# Amp.net
KiCad netlist of a schematic drawn in Altium Designer
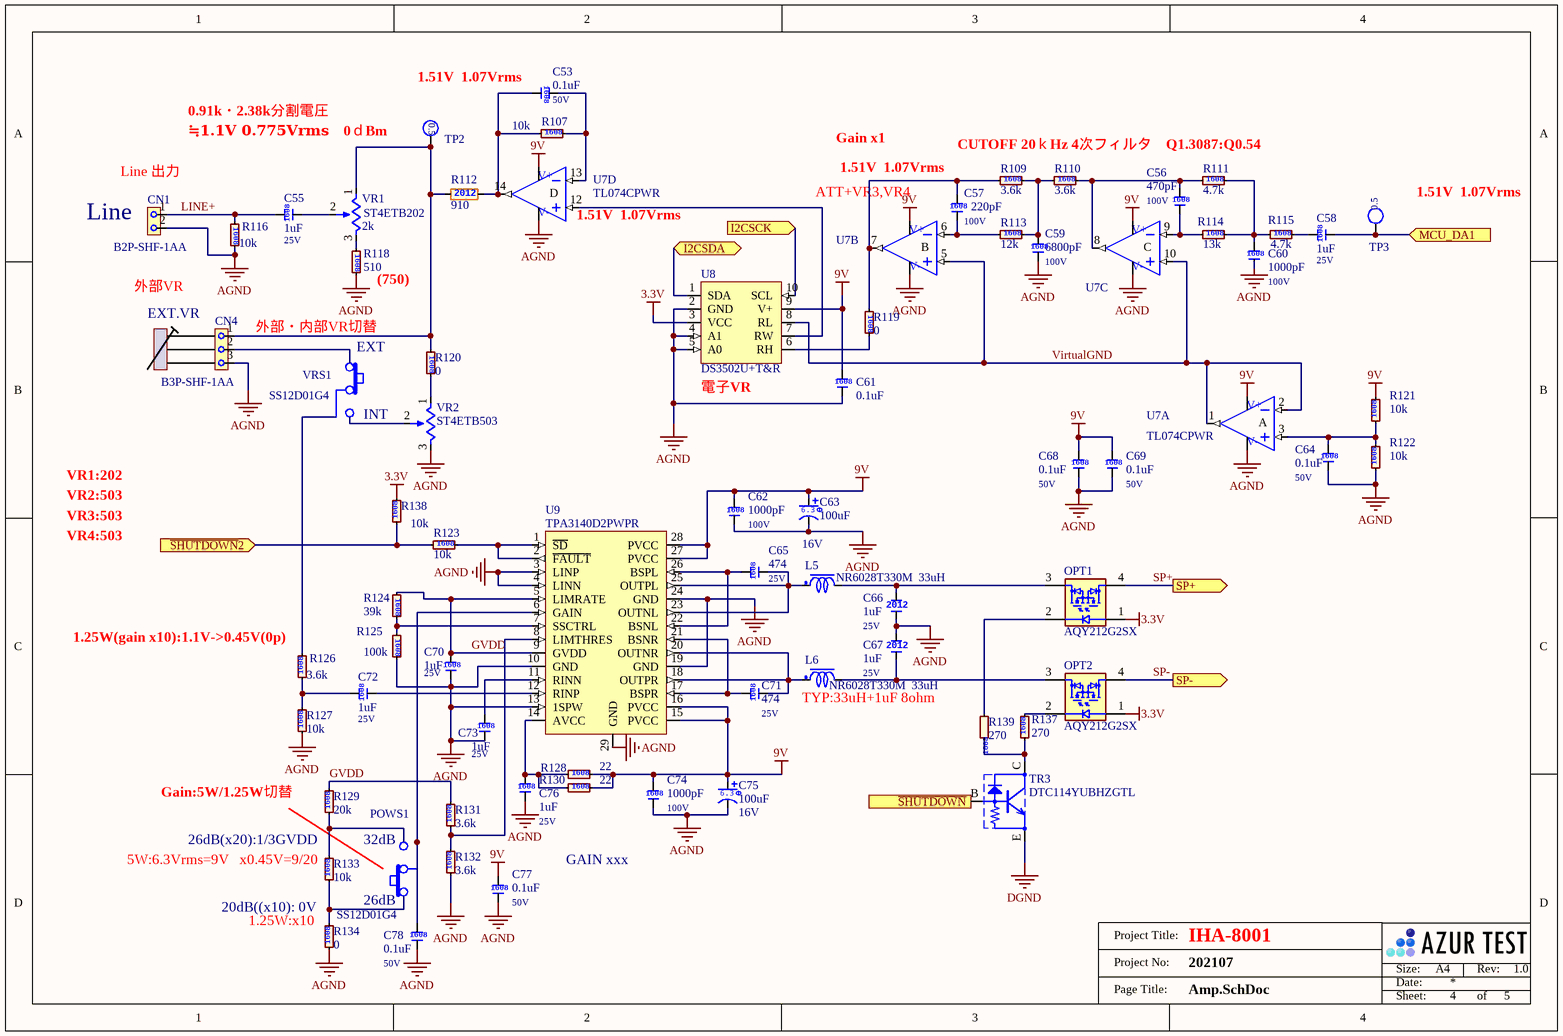
[diagram p0: Amp.SchDoc]

(export (version "E")
  (design (tool "Eeschema 10.0.6"))
  (components
    (comp (ref "C53")
      (value "CGA3E2X7R1H104K080AA")
      (footprint "C1608")
      (description "セラコン1608サイズ")
      (fields (field (name "TAG") "0.1uF") (field (name "VOLTAGE") "50V"))
      (libsource (lib "Audio Prj") (part "C1608"))
    )
    (comp (ref "C55")
      (value "TMK107BJ105MA-T")
      (footprint "C1608")
      (description "セラコン1608サイズ")
      (fields (field (name "TAG") "1uF") (field (name "VOLTAGE") "25V"))
      (libsource (lib "Audio Prj") (part "C1608"))
    )
    (comp (ref "C56")
      (value "GCM1885C2A471JA16D")
      (footprint "C1608")
      (description "セラコン1608サイズ")
      (fields (field (name "TAG") "470pF") (field (name "VOLTAGE") "100V"))
      (libsource (lib "Audio Prj") (part "C1608"))
    )
    (comp (ref "C57")
      (value "GCM1885C2A221JA16D")
      (footprint "C1608")
      (description "セラコン1608サイズ")
      (fields (field (name "TAG") "220pF") (field (name "VOLTAGE") "100V"))
      (libsource (lib "Audio Prj") (part "C1608"))
    )
    (comp (ref "C58")
      (value "TMK107BJ105MA-T")
      (footprint "C1608")
      (description "セラコン1608サイズ")
      (fields (field (name "TAG") "1uF") (field (name "VOLTAGE") "25V"))
      (libsource (lib "Audio Prj") (part "C1608"))
    )
    (comp (ref "C59")
      (value "GCM1885C2A682JA16D")
      (footprint "C1608")
      (description "セラコン1608サイズ")
      (fields (field (name "TAG") "6800pF") (field (name "VOLTAGE") "100V"))
      (libsource (lib "Audio Prj") (part "C1608"))
    )
    (comp (ref "C60")
      (value "GCM1885C2A102JA16D")
      (footprint "C1608")
      (description "セラコン1608サイズ")
      (fields (field (name "TAG") "1000pF") (field (name "VOLTAGE") "100V"))
      (libsource (lib "Audio Prj") (part "C1608"))
    )
    (comp (ref "C61")
      (value "CGA3E2X7R1H104K080AA")
      (footprint "C1608")
      (description "セラコン1608サイズ")
      (fields (field (name "TAG") "0.1uF") (field (name "VOLTAGE") "50V"))
      (libsource (lib "Audio Prj") (part "C1608"))
    )
    (comp (ref "C62")
      (value "GCM1885C2A102JA16D")
      (footprint "C1608")
      (description "セラコン1608サイズ")
      (fields (field (name "TAG") "1000pF") (field (name "VOLTAGE") "100V"))
      (libsource (lib "Audio Prj") (part "C1608"))
    )
    (comp (ref "C63")
      (value "UCQ1C101MCL1GS")
      (footprint "6.6mmX6.6mm")
      (description "6.3φ 電解コンデンサ")
      (fields (field (name "TAG") "100uF") (field (name "VOLTAGE") "16V"))
      (libsource (lib "Audio Prj") (part "6.6 X 6.6"))
    )
    (comp (ref "C64")
      (value "CGA3E2X7R1H104K080AA")
      (footprint "C1608")
      (description "セラコン1608サイズ")
      (fields (field (name "TAG") "0.1uF") (field (name "VOLTAGE") "50V"))
      (libsource (lib "Audio Prj") (part "C1608"))
    )
    (comp (ref "C65")
      (value "UMK107B7474KA-TR")
      (footprint "C1608")
      (description "セラコン1608サイズ")
      (fields (field (name "TAG") "474") (field (name "VOLTAGE") "25V"))
      (libsource (lib "Audio Prj") (part "C1608"))
    )
    (comp (ref "C66")
      (value "TMK212BJ105KG-T")
      (footprint "C2012")
      (description "セラコン2012サイズ")
      (fields (field (name "TAG") "1uF") (field (name "VOLTAGE") "25V"))
      (libsource (lib "Audio") (part "C2012"))
    )
    (comp (ref "C67")
      (value "TMK212BJ105KG-T")
      (footprint "C2012")
      (description "セラコン2012サイズ")
      (fields (field (name "TAG") "1uF") (field (name "VOLTAGE") "25V"))
      (libsource (lib "Audio") (part "C2012"))
    )
    (comp (ref "C68")
      (value "CGA3E2X7R1H104K080AA")
      (footprint "C1608")
      (description "セラコン1608サイズ")
      (fields (field (name "TAG") "0.1uF") (field (name "VOLTAGE") "50V"))
      (libsource (lib "Audio Prj") (part "C1608"))
    )
    (comp (ref "C69")
      (value "CGA3E2X7R1H104K080AA")
      (footprint "C1608")
      (description "セラコン1608サイズ")
      (fields (field (name "TAG") "0.1uF") (field (name "VOLTAGE") "50V"))
      (libsource (lib "Audio Prj") (part "C1608"))
    )
    (comp (ref "C70")
      (value "TMK107BJ105MA-T")
      (footprint "C1608")
      (description "セラコン1608サイズ")
      (fields (field (name "TAG") "1uF") (field (name "VOLTAGE") "25V"))
      (libsource (lib "Audio Prj") (part "C1608"))
    )
    (comp (ref "C71")
      (value "UMK107B7474KA-TR")
      (footprint "C1608")
      (description "セラコン1608サイズ")
      (fields (field (name "TAG") "474") (field (name "VOLTAGE") "25V"))
      (libsource (lib "Audio Prj") (part "C1608"))
    )
    (comp (ref "C72")
      (value "TMK107BJ105MA-T")
      (footprint "C1608")
      (description "セラコン1608サイズ")
      (fields (field (name "TAG") "1uF") (field (name "VOLTAGE") "25V"))
      (libsource (lib "Audio Prj") (part "C1608"))
    )
    (comp (ref "C73")
      (value "TMK107BJ105MA-T")
      (footprint "C1608")
      (description "セラコン1608サイズ")
      (fields (field (name "TAG") "1uF") (field (name "VOLTAGE") "25V"))
      (libsource (lib "Audio Prj") (part "C1608"))
    )
    (comp (ref "C74")
      (value "GCM1885C2A102JA16D")
      (footprint "C1608")
      (description "セラコン1608サイズ")
      (fields (field (name "TAG") "1000pF") (field (name "VOLTAGE") "100V"))
      (libsource (lib "Audio Prj") (part "C1608"))
    )
    (comp (ref "C75")
      (value "UCQ1C101MCL1GS")
      (footprint "6.6mmX6.6mm")
      (description "6.3φ 電解コンデンサ")
      (fields (field (name "TAG") "100uF") (field (name "VOLTAGE") "16V"))
      (libsource (lib "Audio Prj") (part "6.6 X 6.6"))
    )
    (comp (ref "C76")
      (value "TMK107BJ105MA-T")
      (footprint "C1608")
      (description "セラコン1608サイズ")
      (fields (field (name "TAG") "1uF") (field (name "VOLTAGE") "25V"))
      (libsource (lib "Audio Prj") (part "C1608"))
    )
    (comp (ref "C77")
      (value "CGA3E2X7R1H104K080AA")
      (footprint "C1608")
      (description "セラコン1608サイズ")
      (fields (field (name "TAG") "0.1uF") (field (name "VOLTAGE") "50V"))
      (libsource (lib "Audio Prj") (part "C1608"))
    )
    (comp (ref "C78")
      (value "CGA3E2X7R1H104K080AA")
      (footprint "C1608")
      (description "セラコン1608サイズ")
      (fields (field (name "TAG") "0.1uF") (field (name "VOLTAGE") "50V"))
      (libsource (lib "Audio Prj") (part "C1608"))
    )
    (comp (ref "CN1")
      (value "B2P-SHF-1AA")
      (footprint "B2P-SHF-1AA")
      (description "雄,ストレート,1列2ピン")
      (libsource (lib "Audio Prj") (part "B2P-SHF-1AA"))
    )
    (comp (ref "CN4")
      (value "B3P-SHF-1AA")
      (footprint "B3P-SHF-1AA")
      (description "雄,ストレート,1列3ピン")
      (libsource (lib "Audio Prj") (part "B3P-SHF-1AA"))
    )
    (comp (ref "L5")
      (value "NR6028T330M  33uH")
      (footprint "NR6028T")
      (description "Shielded Inductor")
      (libsource (lib "Audio Prj") (part "DR125"))
    )
    (comp (ref "L6")
      (value "NR6028T330M  33uH")
      (footprint "NR6028T")
      (description "Shielded Inductor")
      (libsource (lib "Audio Prj") (part "DR125"))
    )
    (comp (ref "OPT1")
      (value "AQY212G2SX")
      (footprint "SOP4-2.54")
      (description "60V 550mA フォトモス")
      (libsource (lib "Audio Prj") (part "AQY225R2S"))
    )
    (comp (ref "OPT2")
      (value "AQY212G2SX")
      (footprint "SOP4-2.54")
      (description "60V 550mA フォトモス")
      (libsource (lib "Audio Prj") (part "AQY225R2S"))
    )
    (comp (ref "POWS1")
      (value "SS12D01G4")
      (footprint "SS12D01G4")
      (description "SPDTスライドスイッチ")
      (libsource (lib "Audio Prj") (part "SS12D01G4"))
    )
    (comp (ref "R107")
      (value "ERJ-PA3F1002V")
      (footprint "R1608")
      (description "厚膜チップ抵抗1608サイズ")
      (fields (field (name "TAG") "10k"))
      (libsource (lib "") (part "TF1608_2"))
    )
    (comp (ref "R109")
      (value "ERJ-PA3F3601V")
      (footprint "R1608")
      (description "厚膜チップ抵抗1608サイズ")
      (fields (field (name "TAG") "3.6k"))
      (libsource (lib "") (part "TF1608_2"))
    )
    (comp (ref "R110")
      (value "ERJ-PA3F3601V")
      (footprint "R1608")
      (description "厚膜チップ抵抗1608サイズ")
      (fields (field (name "TAG") "3.6k"))
      (libsource (lib "") (part "TF1608_2"))
    )
    (comp (ref "R111")
      (value "ERJ-PA3F4701V")
      (footprint "R1608")
      (description "厚膜チップ抵抗1608サイズ")
      (fields (field (name "TAG") "4.7k"))
      (libsource (lib "") (part "TF1608_2"))
    )
    (comp (ref "R112")
      (value "RK73B2ATTD911J")
      (footprint "R2012")
      (description "薄膜チップ抵抗2012サイズ")
      (fields (field (name "TAG") "910"))
      (libsource (lib "Audio Prj") (part "MF2012"))
    )
    (comp (ref "R113")
      (value "ERJ-PA3F1201V")
      (footprint "R1608")
      (description "厚膜チップ抵抗1608サイズ")
      (fields (field (name "TAG") "12k"))
      (libsource (lib "") (part "TF1608_2"))
    )
    (comp (ref "R114")
      (value "ERJ-PA3F1302V")
      (footprint "R1608")
      (description "厚膜チップ抵抗1608サイズ")
      (fields (field (name "TAG") "13k"))
      (libsource (lib "") (part "TF1608_2"))
    )
    (comp (ref "R115")
      (value "ERJ-PA3F4701V")
      (footprint "R1608")
      (description "厚膜チップ抵抗1608サイズ")
      (fields (field (name "TAG") "4.7k"))
      (libsource (lib "") (part "TF1608_2"))
    )
    (comp (ref "R116")
      (value "ERJ-PA3F1002V")
      (footprint "R1608")
      (description "厚膜チップ抵抗1608サイズ")
      (fields (field (name "TAG") "10k"))
      (libsource (lib "") (part "TF1608_1"))
    )
    (comp (ref "R118")
      (value "ERJ-PA3F5100V")
      (footprint "R1608")
      (description "厚膜チップ抵抗1608サイズ")
      (fields (field (name "TAG") "510"))
      (libsource (lib "") (part "TF1608_1"))
    )
    (comp (ref "R119")
      (value "RK73Z1JTTD")
      (footprint "R1608")
      (description "厚膜チップ抵抗1608サイズ")
      (fields (field (name "TAG") "0"))
      (libsource (lib "") (part "TF1608_1"))
    )
    (comp (ref "R120")
      (value "RK73Z1JTTD")
      (footprint "R1608")
      (description "厚膜チップ抵抗1608サイズ")
      (fields (field (name "TAG") "0"))
      (libsource (lib "") (part "TF1608_1"))
    )
    (comp (ref "R121")
      (value "ERJ-PA3F1002V")
      (footprint "R1608")
      (description "厚膜チップ抵抗1608サイズ")
      (fields (field (name "TAG") "10k"))
      (libsource (lib "Audio Prj") (part "TF1608"))
    )
    (comp (ref "R122")
      (value "ERJ-PA3F1002V")
      (footprint "R1608")
      (description "厚膜チップ抵抗1608サイズ")
      (fields (field (name "TAG") "10k"))
      (libsource (lib "Audio Prj") (part "TF1608"))
    )
    (comp (ref "R123")
      (value "ERJ-PA3F1002V")
      (footprint "R1608")
      (description "厚膜チップ抵抗1608サイズ")
      (fields (field (name "TAG") "10k"))
      (libsource (lib "") (part "TF1608_2"))
    )
    (comp (ref "R124")
      (value "ERJ-PA3F3902V")
      (footprint "R1608")
      (description "厚膜チップ抵抗1608サイズ")
      (fields (field (name "TAG") "39k"))
      (libsource (lib "") (part "TF1608_1"))
    )
    (comp (ref "R125")
      (value "ERJ-PA3F1003V")
      (footprint "R1608")
      (description "厚膜チップ抵抗1608サイズ")
      (fields (field (name "TAG") "100k"))
      (libsource (lib "") (part "TF1608_1"))
    )
    (comp (ref "R126")
      (value "ERJ-PA3F3601V")
      (footprint "R1608")
      (description "厚膜チップ抵抗1608サイズ")
      (fields (field (name "TAG") "3.6k"))
      (libsource (lib "Audio Prj") (part "TF1608"))
    )
    (comp (ref "R127")
      (value "ERJ-PA3F1002V")
      (footprint "R1608")
      (description "厚膜チップ抵抗1608サイズ")
      (fields (field (name "TAG") "10k"))
      (libsource (lib "Audio Prj") (part "TF1608"))
    )
    (comp (ref "R128")
      (value "ERJ-PA3F22R0V")
      (footprint "R1608")
      (description "厚膜チップ抵抗1608サイズ")
      (fields (field (name "TAG") "22"))
      (libsource (lib "") (part "TF1608_2"))
    )
    (comp (ref "R129")
      (value "ERJ-PA3F2002V")
      (footprint "R1608")
      (description "厚膜チップ抵抗1608サイズ")
      (fields (field (name "TAG") "20k"))
      (libsource (lib "Audio Prj") (part "TF1608"))
    )
    (comp (ref "R130")
      (value "ERJ-PA3F22R0V")
      (footprint "R1608")
      (description "厚膜チップ抵抗1608サイズ")
      (fields (field (name "TAG") "22"))
      (libsource (lib "") (part "TF1608_2"))
    )
    (comp (ref "R131")
      (value "ERJ-PA3F3601V")
      (footprint "R1608")
      (description "厚膜チップ抵抗1608サイズ")
      (fields (field (name "TAG") "3.6k"))
      (libsource (lib "Audio Prj") (part "TF1608"))
    )
    (comp (ref "R132")
      (value "ERJ-PA3F3601V")
      (footprint "R1608")
      (description "厚膜チップ抵抗1608サイズ")
      (fields (field (name "TAG") "3.6k"))
      (libsource (lib "Audio Prj") (part "TF1608"))
    )
    (comp (ref "R133")
      (value "ERJ-PA3F1002V")
      (footprint "R1608")
      (description "厚膜チップ抵抗1608サイズ")
      (fields (field (name "TAG") "10k"))
      (libsource (lib "Audio Prj") (part "TF1608"))
    )
    (comp (ref "R134")
      (value "RK73Z1JTTD")
      (footprint "R1608")
      (description "厚膜チップ抵抗1608サイズ")
      (fields (field (name "TAG") "0"))
      (libsource (lib "Audio Prj") (part "TF1608"))
    )
    (comp (ref "R137")
      (value "RR0816P-271-D")
      (footprint "R1608")
      (description "厚膜チップ抵抗1608サイズ")
      (fields (field (name "TAG") "270"))
      (libsource (lib "Audio Prj") (part "TF1608"))
    )
    (comp (ref "R138")
      (value "ERJ-PA3F1002V")
      (footprint "R1608")
      (description "厚膜チップ抵抗1608サイズ")
      (fields (field (name "TAG") "10k"))
      (libsource (lib "Audio Prj") (part "TF1608"))
    )
    (comp (ref "R139")
      (value "RR0816P-271-D")
      (footprint "R1608")
      (description "厚膜チップ抵抗1608サイズ")
      (fields (field (name "TAG") "270"))
      (libsource (lib "") (part "TF1608_2"))
    )
    (comp (ref "TP2")
      (value "TP0.5mm")
      (footprint "TP0.5mm")
      (description "Test-Point 0.5mm")
      (libsource (lib "Audio Prj") (part "TP0.5mm"))
    )
    (comp (ref "TP3")
      (value "TP0.5mm")
      (footprint "TP0.5mm")
      (description "Test-Point 0.5mm")
      (libsource (lib "Audio Prj") (part "TP0.5mm"))
    )
    (comp (ref "TR3")
      (value "DTC114YUBHZGTL")
      (footprint "SOT-323F")
      (description "NPN  TR 0.1A SC85 2x2.1 SOC323")
      (libsource (lib "Audio Prj") (part "DTC114YUBHZGTL"))
    )
    (comp (ref "U7")
      (value "TL074CPWR")
      (footprint "TSSOP14")
      (description "IC OPAMP JFET 4 CIRCUIT 14TSSOP")
      (libsource (lib "Audio Prj") (part "TL084CPT"))
    )
    (comp (ref "U8")
      (value "DS3502U+T&R")
      (footprint "MSOP10")
      (description "IC DGTL POT 10KOHM 128TAP 10UMAX")
      (libsource (lib "Audio Prj") (part "DS3502U+T&R"))
    )
    (comp (ref "U9")
      (value "TPA3140D2PWPR")
      (footprint "TSSOP28")
      (description "IC AMP CLASS D STER 10W 28HTSSOP")
      (libsource (lib "Audio Prj") (part "TPA3140D2PWPR"))
    )
    (comp (ref "VR1")
      (value "ST4ETB202")
      (footprint "ST4ETB202")
      (description "CERMET TRIMMER  Top adjustmet")
      (fields (field (name "TAG") "2k"))
      (libsource (lib "Audio Prj") (part "ST-32EA**"))
    )
    (comp (ref "VR2")
      (value "ST4ETB503")
      (footprint "ST4ETB202")
      (description "CERMET TRIMMER  Top adjustmet")
      (libsource (lib "Audio Prj") (part "ST-32EA**"))
    )
    (comp (ref "VRS1")
      (value "SS12D01G4")
      (footprint "SS12D01G4")
      (description "SPDTスライドスイッチ")
      (libsource (lib "Audio Prj") (part "SS12D01G4"))
    )
  )
  (nets
    (net (code "1") (name "/GVDD") (class "Default")
      (node (ref "C70") (pin "2") (pinfunction "2_2") (pintype "passive"))
      (node (ref "R124") (pin "1") (pinfunction "1_1") (pintype "passive"))
      (node (ref "R129") (pin "2") (pinfunction "2_2") (pintype "passive"))
      (node (ref "R131") (pin "2") (pinfunction "2_2") (pintype "passive"))
      (node (ref "U9") (pin "5") (pinfunction "LIMRATE_5") (pintype "input"))
      (node (ref "U9") (pin "9") (pinfunction "GVDD_9") (pintype "power_in"))
    )
    (net (code "2") (name "/I2CSCK") (class "Default")
      (node (ref "U8") (pin "10") (pinfunction "SCL_10") (pintype "input"))
    )
    (net (code "3") (name "/I2CSDA") (class "Default")
      (node (ref "U8") (pin "1") (pinfunction "SDA_1") (pintype "bidirectional"))
    )
    (net (code "4") (name "/LINE+") (class "Default")
      (node (ref "C55") (pin "2") (pinfunction "2_2") (pintype "passive"))
      (node (ref "CN1") (pin "1") (pinfunction "1_1") (pintype "passive"))
      (node (ref "R116") (pin "1") (pinfunction "1_1") (pintype "passive"))
    )
    (net (code "5") (name "/MCU_DA1") (class "Default")
      (node (ref "C58") (pin "1") (pinfunction "1_1") (pintype "passive"))
      (node (ref "TP3") (pin "1") (pinfunction "1_1") (pintype "passive"))
    )
    (net (code "6") (name "/SP+") (class "Default")
      (node (ref "OPT1") (pin "4") (pinfunction "4_4") (pintype "passive"))
    )
    (net (code "7") (name "/SP-") (class "Default")
      (node (ref "OPT2") (pin "4") (pinfunction "4_4") (pintype "passive"))
    )
    (net (code "8") (name "/VirtualGND") (class "Default")
      (node (ref "U7") (pin "1") (pinfunction "OUT_1") (pintype "output"))
      (node (ref "U7") (pin "10") (pinfunction "IN+_10") (pintype "input"))
      (node (ref "U7") (pin "2") (pinfunction "IN-_2") (pintype "input"))
      (node (ref "U7") (pin "5") (pinfunction "IN+_5") (pintype "input"))
      (node (ref "U8") (pin "8") (pinfunction "RL_8") (pintype "passive"))
    )
    (net (code "9") (name "/~{SHUTDOWN}") (class "Default")
      (node (ref "TR3") (pin "B") (pinfunction "IN_B") (pintype "passive"))
    )
    (net (code "10") (name "/~{SHUTDOWN}2") (class "Default")
      (node (ref "R123") (pin "1") (pinfunction "1_1") (pintype "passive"))
      (node (ref "R138") (pin "1") (pinfunction "1_1") (pintype "passive"))
    )
    (net (code "11") (name "3.3V") (class "Default")
      (node (ref "OPT1") (pin "1") (pinfunction "1_1") (pintype "passive"))
      (node (ref "OPT2") (pin "1") (pinfunction "1_1") (pintype "passive"))
      (node (ref "R138") (pin "2") (pinfunction "2_2") (pintype "passive"))
      (node (ref "U8") (pin "3") (pinfunction "VCC_3") (pintype "power_in"))
    )
    (net (code "12") (name "9V") (class "Default")
      (node (ref "C61") (pin "2") (pinfunction "2_2") (pintype "passive"))
      (node (ref "C62") (pin "2") (pinfunction "2_2") (pintype "passive"))
      (node (ref "C63") (pin "+") (pinfunction "1_+") (pintype "passive"))
      (node (ref "C68") (pin "2") (pinfunction "2_2") (pintype "passive"))
      (node (ref "C69") (pin "2") (pinfunction "2_2") (pintype "passive"))
      (node (ref "C74") (pin "2") (pinfunction "2_2") (pintype "passive"))
      (node (ref "C75") (pin "+") (pinfunction "1_+") (pintype "passive"))
      (node (ref "C77") (pin "2") (pinfunction "2_2") (pintype "passive"))
      (node (ref "R121") (pin "2") (pinfunction "2_2") (pintype "passive"))
      (node (ref "R128") (pin "2") (pinfunction "2_2") (pintype "passive"))
      (node (ref "R130") (pin "2") (pinfunction "2_2") (pintype "passive"))
      (node (ref "U7") (pin "4") (pinfunction "V+_4") (pintype "power_in"))
      (node (ref "U8") (pin "9") (pinfunction "V+_9") (pintype "power_in"))
      (node (ref "U9") (pin "15") (pinfunction "PVCC_15") (pintype "power_in"))
      (node (ref "U9") (pin "16") (pinfunction "PVCC_16") (pintype "power_in"))
      (node (ref "U9") (pin "27") (pinfunction "PVCC_27") (pintype "power_in"))
      (node (ref "U9") (pin "28") (pinfunction "PVCC_28") (pintype "power_in"))
    )
    (net (code "13") (name "AGND") (class "Default")
      (node (ref "C59") (pin "1") (pinfunction "1_1") (pintype "passive"))
      (node (ref "C60") (pin "1") (pinfunction "1_1") (pintype "passive"))
      (node (ref "C61") (pin "1") (pinfunction "1_1") (pintype "passive"))
      (node (ref "C62") (pin "1") (pinfunction "1_1") (pintype "passive"))
      (node (ref "C63") (pin "-") (pinfunction "2_-") (pintype "passive"))
      (node (ref "C64") (pin "1") (pinfunction "1_1") (pintype "passive"))
      (node (ref "C66") (pin "1") (pinfunction "1_1") (pintype "passive"))
      (node (ref "C67") (pin "2") (pinfunction "2_2") (pintype "passive"))
      (node (ref "C68") (pin "1") (pinfunction "1_1") (pintype "passive"))
      (node (ref "C69") (pin "1") (pinfunction "1_1") (pintype "passive"))
      (node (ref "C70") (pin "1") (pinfunction "1_1") (pintype "passive"))
      (node (ref "C73") (pin "1") (pinfunction "1_1") (pintype "passive"))
      (node (ref "C74") (pin "1") (pinfunction "1_1") (pintype "passive"))
      (node (ref "C75") (pin "-") (pinfunction "2_-") (pintype "passive"))
      (node (ref "C76") (pin "1") (pinfunction "1_1") (pintype "passive"))
      (node (ref "C77") (pin "1") (pinfunction "1_1") (pintype "passive"))
      (node (ref "C78") (pin "1") (pinfunction "1_1") (pintype "passive"))
      (node (ref "CN1") (pin "2") (pinfunction "2_2") (pintype "passive"))
      (node (ref "CN4") (pin "3") (pinfunction "3_3") (pintype "passive"))
      (node (ref "R116") (pin "2") (pinfunction "2_2") (pintype "passive"))
      (node (ref "R118") (pin "2") (pinfunction "2_2") (pintype "passive"))
      (node (ref "R122") (pin "1") (pinfunction "1_1") (pintype "passive"))
      (node (ref "R125") (pin "2") (pinfunction "2_2") (pintype "passive"))
      (node (ref "R127") (pin "1") (pinfunction "1_1") (pintype "passive"))
      (node (ref "R132") (pin "1") (pinfunction "1_1") (pintype "passive"))
      (node (ref "R134") (pin "1") (pinfunction "1_1") (pintype "passive"))
      (node (ref "U7") (pin "11") (pinfunction "V-_11") (pintype "power_in"))
      (node (ref "U8") (pin "2") (pinfunction "GND_2") (pintype "power_in"))
      (node (ref "U8") (pin "4") (pinfunction "A1_4") (pintype "input"))
      (node (ref "U8") (pin "5") (pinfunction "A0_5") (pintype "input"))
      (node (ref "U9") (pin "10") (pinfunction "GND_10") (pintype "power_in"))
      (node (ref "U9") (pin "13") (pinfunction "1SPW_13") (pintype "input"))
      (node (ref "U9") (pin "19") (pinfunction "GND_19") (pintype "power_in"))
      (node (ref "U9") (pin "24") (pinfunction "GND_24") (pintype "power_in"))
      (node (ref "U9") (pin "29") (pinfunction "GND_29") (pintype "power_in"))
      (node (ref "U9") (pin "3") (pinfunction "LINP_3") (pintype "input"))
      (node (ref "U9") (pin "4") (pinfunction "LINN_4") (pintype "input"))
      (node (ref "VR2") (pin "3") (pinfunction "3_3") (pintype "passive"))
    )
    (net (code "14") (name "DGND") (class "Default")
      (node (ref "TR3") (pin "E") (pinfunction "E_E") (pintype "passive"))
    )
    (net (code "15") (name "Net-(C55-Pad1)") (class "Default")
      (node (ref "C55") (pin "1") (pinfunction "1_1") (pintype "passive"))
      (node (ref "VR1") (pin "2") (pinfunction "2_2") (pintype "passive"))
    )
    (net (code "16") (name "Net-(C58-Pad2)") (class "Default")
      (node (ref "C58") (pin "2") (pinfunction "2_2") (pintype "passive"))
      (node (ref "R115") (pin "2") (pinfunction "2_2") (pintype "passive"))
    )
    (net (code "17") (name "Net-(C59-Pad2)") (class "Default")
      (node (ref "C59") (pin "2") (pinfunction "2_2") (pintype "passive"))
      (node (ref "R109") (pin "2") (pinfunction "2_2") (pintype "passive"))
      (node (ref "R110") (pin "1") (pinfunction "1_1") (pintype "passive"))
      (node (ref "R113") (pin "2") (pinfunction "2_2") (pintype "passive"))
    )
    (net (code "18") (name "Net-(C60-Pad2)") (class "Default")
      (node (ref "C60") (pin "2") (pinfunction "2_2") (pintype "passive"))
      (node (ref "R111") (pin "2") (pinfunction "2_2") (pintype "passive"))
      (node (ref "R114") (pin "2") (pinfunction "2_2") (pintype "passive"))
      (node (ref "R115") (pin "1") (pinfunction "1_1") (pintype "passive"))
    )
    (net (code "19") (name "Net-(C66-Pad2)") (class "Default")
      (node (ref "C66") (pin "2") (pinfunction "2_2") (pintype "passive"))
      (node (ref "L5") (pin "2") (pinfunction "2_2") (pintype "passive"))
      (node (ref "OPT1") (pin "3") (pinfunction "3_3") (pintype "passive"))
    )
    (net (code "20") (name "Net-(C67-Pad1)") (class "Default")
      (node (ref "C67") (pin "1") (pinfunction "1_1") (pintype "passive"))
      (node (ref "L6") (pin "2") (pinfunction "2_2") (pintype "passive"))
      (node (ref "OPT2") (pin "3") (pinfunction "3_3") (pintype "passive"))
    )
    (net (code "21") (name "Net-(C72-Pad2)") (class "Default")
      (node (ref "C72") (pin "2") (pinfunction "2_2") (pintype "passive"))
      (node (ref "R126") (pin "1") (pinfunction "1_1") (pintype "passive"))
      (node (ref "R127") (pin "2") (pinfunction "2_2") (pintype "passive"))
    )
    (net (code "22") (name "Net-(CN4-Pad1)") (class "Default")
      (node (ref "CN4") (pin "1") (pinfunction "1_1") (pintype "passive"))
      (node (ref "R112") (pin "1") (pinfunction "1_1") (pintype "passive"))
      (node (ref "R120") (pin "1") (pinfunction "1_1") (pintype "passive"))
      (node (ref "TP2") (pin "1") (pinfunction "1_1") (pintype "passive"))
      (node (ref "VR1") (pin "1") (pinfunction "1_1") (pintype "passive"))
    )
    (net (code "23") (name "Net-(CN4-Pad2)") (class "Default")
      (node (ref "CN4") (pin "2") (pinfunction "2_2") (pintype "passive"))
      (node (ref "VRS1") (pin "1") (pinfunction "1_1") (pintype "passive"))
    )
    (net (code "24") (name "Net-(OPT1-Pad2)") (class "Default")
      (node (ref "OPT1") (pin "2") (pinfunction "2_2") (pintype "passive"))
      (node (ref "R139") (pin "2") (pinfunction "2_2") (pintype "passive"))
    )
    (net (code "25") (name "Net-(OPT2-Pad2)") (class "Default")
      (node (ref "OPT2") (pin "2") (pinfunction "2_2") (pintype "passive"))
      (node (ref "R137") (pin "2") (pinfunction "2_2") (pintype "passive"))
    )
    (net (code "26") (name "Net-(POWS1-Pad1)") (class "Default")
      (node (ref "POWS1") (pin "1") (pinfunction "1_1") (pintype "passive"))
      (node (ref "R133") (pin "1") (pinfunction "1_1") (pintype "passive"))
      (node (ref "R134") (pin "2") (pinfunction "2_2") (pintype "passive"))
    )
    (net (code "27") (name "Net-(POWS1-Pad3)") (class "Default")
      (node (ref "POWS1") (pin "3") (pinfunction "3_3") (pintype "passive"))
      (node (ref "R129") (pin "1") (pinfunction "1_1") (pintype "passive"))
      (node (ref "R133") (pin "2") (pinfunction "2_2") (pintype "passive"))
    )
    (net (code "28") (name "Net-(R118-Pad1)") (class "Default")
      (node (ref "R118") (pin "1") (pinfunction "1_1") (pintype "passive"))
      (node (ref "VR1") (pin "3") (pinfunction "3_3") (pintype "passive"))
    )
    (net (code "29") (name "Net-(R120-Pad2)") (class "Default")
      (node (ref "R120") (pin "2") (pinfunction "2_2") (pintype "passive"))
      (node (ref "VR2") (pin "1") (pinfunction "1_1") (pintype "passive"))
    )
    (net (code "30") (name "Net-(R126-Pad2)") (class "Default")
      (node (ref "R126") (pin "2") (pinfunction "2_2") (pintype "passive"))
      (node (ref "VRS1") (pin "2") (pinfunction "2_2") (pintype "passive"))
    )
    (net (code "31") (name "Net-(R137-Pad1)") (class "Default")
      (node (ref "R137") (pin "1") (pinfunction "1_1") (pintype "passive"))
      (node (ref "R139") (pin "1") (pinfunction "1_1") (pintype "passive"))
      (node (ref "TR3") (pin "C") (pinfunction "C_C") (pintype "passive"))
    )
    (net (code "32") (name "Net-(U7A-IN+)") (class "Default")
      (node (ref "C64") (pin "2") (pinfunction "2_2") (pintype "passive"))
      (node (ref "R121") (pin "1") (pinfunction "1_1") (pintype "passive"))
      (node (ref "R122") (pin "2") (pinfunction "2_2") (pintype "passive"))
      (node (ref "U7") (pin "3") (pinfunction "IN+_3") (pintype "input"))
    )
    (net (code "33") (name "Net-(U7B-IN-)") (class "Default")
      (node (ref "C57") (pin "1") (pinfunction "1_1") (pintype "passive"))
      (node (ref "R113") (pin "1") (pinfunction "1_1") (pintype "passive"))
      (node (ref "U7") (pin "6") (pinfunction "IN-_6") (pintype "input"))
    )
    (net (code "34") (name "Net-(U7B-OUT)") (class "Default")
      (node (ref "C57") (pin "2") (pinfunction "2_2") (pintype "passive"))
      (node (ref "R109") (pin "1") (pinfunction "1_1") (pintype "passive"))
      (node (ref "R119") (pin "1") (pinfunction "1_1") (pintype "passive"))
      (node (ref "U7") (pin "7") (pinfunction "OUT_7") (pintype "output"))
    )
    (net (code "35") (name "Net-(U7C-IN-)") (class "Default")
      (node (ref "C56") (pin "1") (pinfunction "1_1") (pintype "passive"))
      (node (ref "R114") (pin "1") (pinfunction "1_1") (pintype "passive"))
      (node (ref "U7") (pin "9") (pinfunction "IN-_9") (pintype "input"))
    )
    (net (code "36") (name "Net-(U7C-OUT)") (class "Default")
      (node (ref "C56") (pin "2") (pinfunction "2_2") (pintype "passive"))
      (node (ref "R110") (pin "2") (pinfunction "2_2") (pintype "passive"))
      (node (ref "R111") (pin "1") (pinfunction "1_1") (pintype "passive"))
      (node (ref "U7") (pin "8") (pinfunction "OUT_8") (pintype "output"))
    )
    (net (code "37") (name "Net-(U7D-IN+)") (class "Default")
      (node (ref "U7") (pin "12") (pinfunction "IN+_12") (pintype "input"))
      (node (ref "U8") (pin "7") (pinfunction "RW_7") (pintype "passive"))
    )
    (net (code "38") (name "Net-(U7D-IN-)") (class "Default")
      (node (ref "C53") (pin "2") (pinfunction "2_2") (pintype "passive"))
      (node (ref "R107") (pin "2") (pinfunction "2_2") (pintype "passive"))
      (node (ref "U7") (pin "13") (pinfunction "IN-_13") (pintype "input"))
    )
    (net (code "39") (name "Net-(U7D-OUT)") (class "Default")
      (node (ref "C53") (pin "1") (pinfunction "1_1") (pintype "passive"))
      (node (ref "R107") (pin "1") (pinfunction "1_1") (pintype "passive"))
      (node (ref "R112") (pin "2") (pinfunction "2_2") (pintype "passive"))
      (node (ref "U7") (pin "14") (pinfunction "OUT_14") (pintype "output"))
    )
    (net (code "40") (name "Net-(U8-RH)") (class "Default")
      (node (ref "R119") (pin "2") (pinfunction "2_2") (pintype "passive"))
      (node (ref "U8") (pin "6") (pinfunction "RH_6") (pintype "passive"))
    )
    (net (code "41") (name "Net-(U9-AVCC)") (class "Default")
      (node (ref "C76") (pin "2") (pinfunction "2_2") (pintype "passive"))
      (node (ref "R128") (pin "1") (pinfunction "1_1") (pintype "passive"))
      (node (ref "R130") (pin "1") (pinfunction "1_1") (pintype "passive"))
      (node (ref "U9") (pin "14") (pinfunction "AVCC_14") (pintype "power_in"))
    )
    (net (code "42") (name "Net-(U9-BSNL)") (class "Default")
      (node (ref "C65") (pin "2") (pinfunction "2_2") (pintype "passive"))
      (node (ref "U9") (pin "22") (pinfunction "BSNL_22") (pintype "input"))
      (node (ref "U9") (pin "26") (pinfunction "BSPL_26") (pintype "input"))
    )
    (net (code "43") (name "Net-(U9-BSNR)") (class "Default")
      (node (ref "C71") (pin "2") (pinfunction "2_2") (pintype "passive"))
      (node (ref "U9") (pin "17") (pinfunction "BSPR_17") (pintype "input"))
      (node (ref "U9") (pin "21") (pinfunction "BSNR_21") (pintype "input"))
    )
    (net (code "44") (name "Net-(U9-GAIN)") (class "Default")
      (node (ref "C78") (pin "2") (pinfunction "2_2") (pintype "passive"))
      (node (ref "POWS1") (pin "2") (pinfunction "2_2") (pintype "passive"))
      (node (ref "U9") (pin "6") (pinfunction "GAIN_6") (pintype "input"))
    )
    (net (code "45") (name "Net-(U9-LIMTHRES)") (class "Default")
      (node (ref "R131") (pin "1") (pinfunction "1_1") (pintype "passive"))
      (node (ref "R132") (pin "2") (pinfunction "2_2") (pintype "passive"))
      (node (ref "U9") (pin "8") (pinfunction "LIMTHRES_8") (pintype "input"))
    )
    (net (code "46") (name "Net-(U9-OUTNL)") (class "Default")
      (node (ref "C65") (pin "1") (pinfunction "1_1") (pintype "passive"))
      (node (ref "L5") (pin "1") (pinfunction "1_1") (pintype "passive"))
      (node (ref "U9") (pin "23") (pinfunction "OUTNL_23") (pintype "output"))
      (node (ref "U9") (pin "25") (pinfunction "OUTPL_25") (pintype "output"))
    )
    (net (code "47") (name "Net-(U9-OUTNR)") (class "Default")
      (node (ref "C71") (pin "1") (pinfunction "1_1") (pintype "passive"))
      (node (ref "L6") (pin "1") (pinfunction "1_1") (pintype "passive"))
      (node (ref "U9") (pin "18") (pinfunction "OUTPR_18") (pintype "output"))
      (node (ref "U9") (pin "20") (pinfunction "OUTNR_20") (pintype "output"))
    )
    (net (code "48") (name "Net-(U9-RINN)") (class "Default")
      (node (ref "C73") (pin "2") (pinfunction "2_2") (pintype "passive"))
      (node (ref "U9") (pin "11") (pinfunction "RINN_11") (pintype "input"))
    )
    (net (code "49") (name "Net-(U9-RINP)") (class "Default")
      (node (ref "C72") (pin "1") (pinfunction "1_1") (pintype "passive"))
      (node (ref "U9") (pin "12") (pinfunction "RINP_12") (pintype "input"))
    )
    (net (code "50") (name "Net-(U9-SSCTRL)") (class "Default")
      (node (ref "R124") (pin "2") (pinfunction "2_2") (pintype "passive"))
      (node (ref "R125") (pin "1") (pinfunction "1_1") (pintype "passive"))
      (node (ref "U9") (pin "7") (pinfunction "SSCTRL_7") (pintype "input"))
    )
    (net (code "51") (name "Net-(U9-~{FAULT})") (class "Default")
      (node (ref "R123") (pin "2") (pinfunction "2_2") (pintype "passive"))
      (node (ref "U9") (pin "1") (pinfunction "~{SD}_1") (pintype "input"))
      (node (ref "U9") (pin "2") (pinfunction "~{FAULT}_2") (pintype "output"))
    )
    (net (code "52") (name "Net-(VR2-Pad2)") (class "Default")
      (node (ref "VR2") (pin "2") (pinfunction "2_2") (pintype "passive"))
      (node (ref "VRS1") (pin "3") (pinfunction "3_3") (pintype "passive"))
    )
  )
)
